# Left.net
KiCad netlist of a schematic drawn in Altium Designer
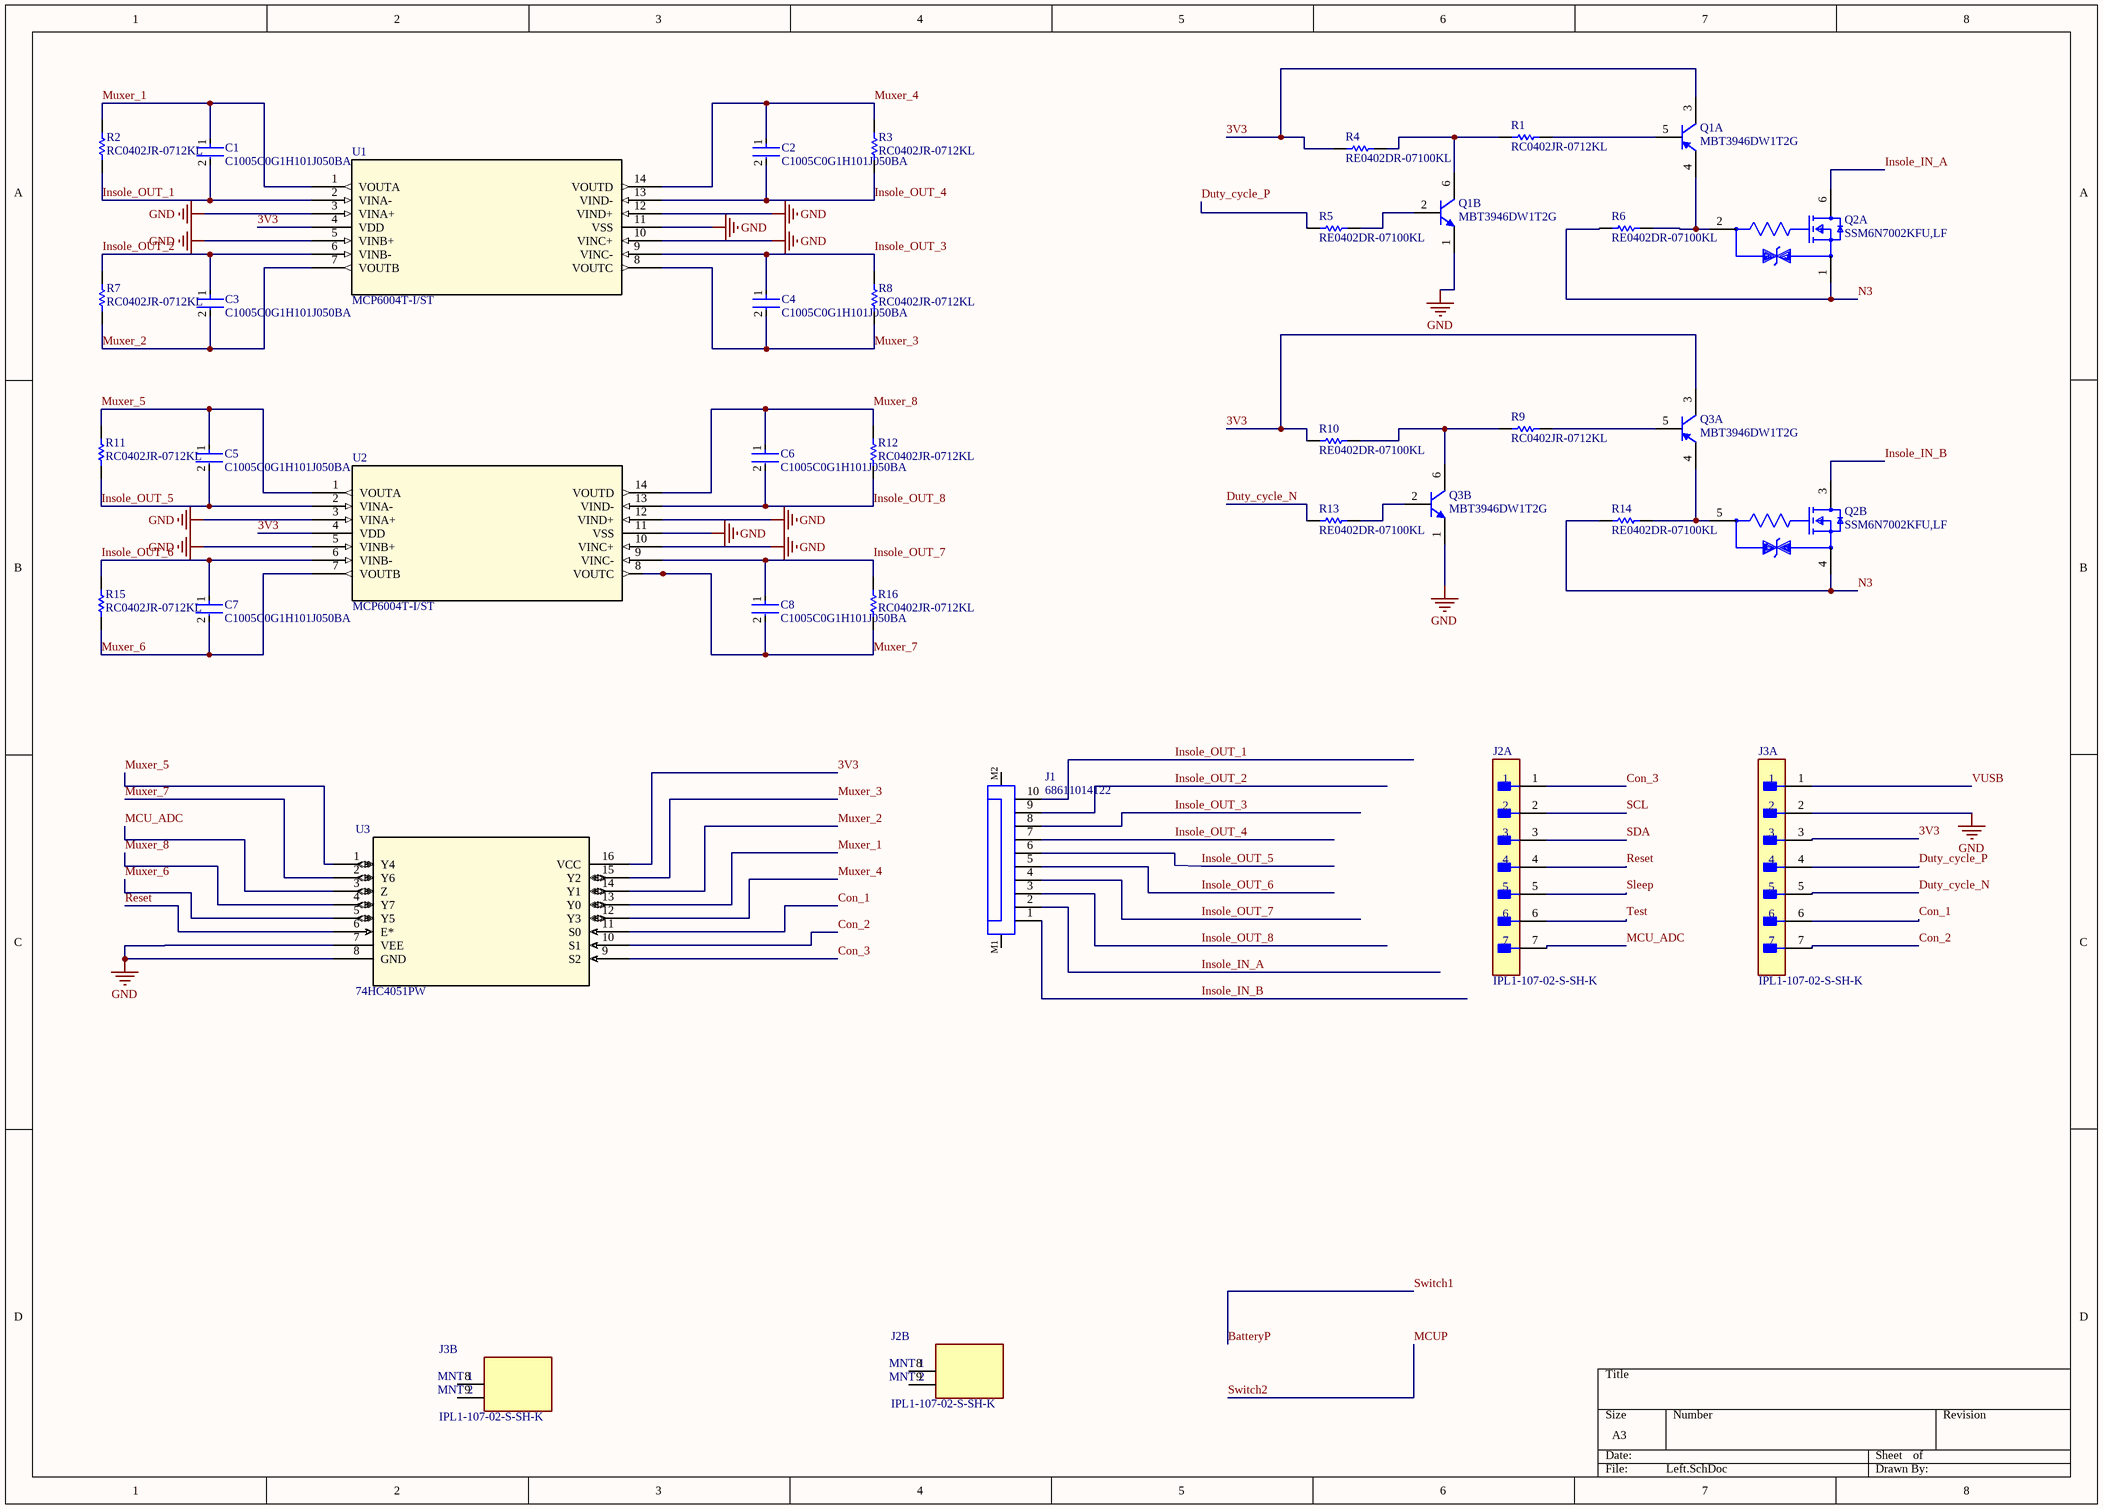
[diagram p0: Left.SchDoc]

(export (version "E")
  (design (tool "Eeschema 10.0.6"))
  (components
    (comp (ref "C1")
      (value "C1005C0G1H101J050BA")
      (footprint "FP-C1005-050-0_05-MFG")
      (description "Multilayer Ceramic Capacitors 100pF ±5% 50V C0G SMD 0402")
      (fields (field (name "TOLERANCE") "5%") (field (name "VOLTAGE") "50V"))
      (libsource (lib "Altium Content Vault") (part "b4654b650e69147ec39a6b967a45e02"))
    )
    (comp (ref "C2")
      (value "C1005C0G1H101J050BA")
      (footprint "FP-C1005-050-0_05-MFG")
      (description "Multilayer Ceramic Capacitors 100pF ±5% 50V C0G SMD 0402")
      (fields (field (name "TOLERANCE") "5%") (field (name "VOLTAGE") "50V"))
      (libsource (lib "Altium Content Vault") (part "b4654b650e69147ec39a6b967a45e02"))
    )
    (comp (ref "C3")
      (value "C1005C0G1H101J050BA")
      (footprint "FP-C1005-050-0_05-MFG")
      (description "Multilayer Ceramic Capacitors 100pF ±5% 50V C0G SMD 0402")
      (fields (field (name "TOLERANCE") "5%") (field (name "VOLTAGE") "50V"))
      (libsource (lib "Altium Content Vault") (part "b4654b650e69147ec39a6b967a45e02"))
    )
    (comp (ref "C4")
      (value "C1005C0G1H101J050BA")
      (footprint "FP-C1005-050-0_05-MFG")
      (description "Multilayer Ceramic Capacitors 100pF ±5% 50V C0G SMD 0402")
      (fields (field (name "TOLERANCE") "5%") (field (name "VOLTAGE") "50V"))
      (libsource (lib "Altium Content Vault") (part "b4654b650e69147ec39a6b967a45e02"))
    )
    (comp (ref "C5")
      (value "C1005C0G1H101J050BA")
      (footprint "FP-C1005-050-0_05-MFG")
      (description "Multilayer Ceramic Capacitors 100pF ±5% 50V C0G SMD 0402")
      (fields (field (name "TOLERANCE") "5%") (field (name "VOLTAGE") "50V"))
      (libsource (lib "Altium Content Vault") (part "b4654b650e69147ec39a6b967a45e02"))
    )
    (comp (ref "C6")
      (value "C1005C0G1H101J050BA")
      (footprint "FP-C1005-050-0_05-MFG")
      (description "Multilayer Ceramic Capacitors 100pF ±5% 50V C0G SMD 0402")
      (fields (field (name "TOLERANCE") "5%") (field (name "VOLTAGE") "50V"))
      (libsource (lib "Altium Content Vault") (part "b4654b650e69147ec39a6b967a45e02"))
    )
    (comp (ref "C7")
      (value "C1005C0G1H101J050BA")
      (footprint "FP-C1005-050-0_05-MFG")
      (description "Multilayer Ceramic Capacitors 100pF ±5% 50V C0G SMD 0402")
      (fields (field (name "TOLERANCE") "5%") (field (name "VOLTAGE") "50V"))
      (libsource (lib "Altium Content Vault") (part "b4654b650e69147ec39a6b967a45e02"))
    )
    (comp (ref "C8")
      (value "C1005C0G1H101J050BA")
      (footprint "FP-C1005-050-0_05-MFG")
      (description "Multilayer Ceramic Capacitors 100pF ±5% 50V C0G SMD 0402")
      (fields (field (name "TOLERANCE") "5%") (field (name "VOLTAGE") "50V"))
      (libsource (lib "Altium Content Vault") (part "b4654b650e69147ec39a6b967a45e02"))
    )
    (comp (ref "J1")
      (value "68611014122")
      (footprint "68611014122")
      (description "68611014122 FPC connect for left")
      (libsource (lib "Altium Content Vault") (part "FPC - 10P - 2MP"))
    )
    (comp (ref "J2")
      (value "IPL1-107-02-S-SH-K")
      (footprint "FP-IPL1-107-02-S-SH-K-0")
      (description "7 Position 1 Row .100\" (2.54 mm) pitch connector")
      (libsource (lib "Altium Content Vault") (part "780f130bdd63e82a3e741ceb73adf18"))
    )
    (comp (ref "J3")
      (value "IPL1-107-02-S-SH-K")
      (footprint "FP-IPL1-107-02-S-SH-K-0")
      (description "7 Position 1 Row .100\" (2.54 mm) pitch connector")
      (libsource (lib "Altium Content Vault") (part "780f130bdd63e82a3e741ceb73adf18"))
    )
    (comp (ref "Q1")
      (value "MBT3946DW1T2G")
      (footprint "ONSC-SC70-6-419B-02_W_V")
      (description "Complementary General Purpose Transistors, 6-Pin SC70, Pb-Free, Tape and Reel")
      (fields (field (name "MANUFACTURER") "On Semiconductor"))
      (libsource (lib "Altium Content Vault") (part "ONSC-NPN_PNP-6"))
    )
    (comp (ref "Q2")
      (value "SSM6N7002KFU,LF")
      (footprint "FP-SSOP6-P-0_65A-MFG")
      (description "MOSFET 2N-CH 60V 0.3A")
      (libsource (lib "Altium Content Vault") (part "088aa6ac103fdeebe0d1c52ece6b7b9"))
    )
    (comp (ref "Q3")
      (value "MBT3946DW1T2G")
      (footprint "ONSC-SC70-6-419B-02_W_V")
      (description "Complementary General Purpose Transistors, 6-Pin SC70, Pb-Free, Tape and Reel")
      (fields (field (name "MANUFACTURER") "On Semiconductor"))
      (libsource (lib "Altium Content Vault") (part "ONSC-NPN_PNP-6"))
    )
    (comp (ref "R1")
      (value "RC0402JR-0712KL")
      (footprint "RESC1005X40X25NL05T10")
      (description "12K resistor")
      (fields (field (name "MANUFACTURER") "Yageo / Phycomp"))
      (libsource (lib "Altium Content Vault") (part "RES"))
    )
    (comp (ref "R2")
      (value "RC0402JR-0712KL")
      (footprint "RESC1005X40X25NL05T10")
      (description "12K resistor")
      (fields (field (name "MANUFACTURER") "Yageo / Phycomp"))
      (libsource (lib "Altium Content Vault") (part "RES"))
    )
    (comp (ref "R3")
      (value "RC0402JR-0712KL")
      (footprint "RESC1005X40X25NL05T10")
      (description "12K resistor")
      (fields (field (name "MANUFACTURER") "Yageo / Phycomp"))
      (libsource (lib "Altium Content Vault") (part "RES"))
    )
    (comp (ref "R4")
      (value "RE0402DR-07100KL")
      (footprint "RESC1005X37X25ML05T10")
      (description "100K resistor")
      (fields (field (name "MANUFACTURER") "Yageo / Phycomp"))
      (libsource (lib "Altium Content Vault") (part "RES"))
    )
    (comp (ref "R5")
      (value "RE0402DR-07100KL")
      (footprint "RESC1005X37X25ML05T10")
      (description "100K resistor")
      (fields (field (name "MANUFACTURER") "Yageo / Phycomp"))
      (libsource (lib "Altium Content Vault") (part "RES"))
    )
    (comp (ref "R6")
      (value "RE0402DR-07100KL")
      (footprint "RESC1005X37X25ML05T10")
      (description "100K resistor")
      (fields (field (name "MANUFACTURER") "Yageo / Phycomp"))
      (libsource (lib "Altium Content Vault") (part "RES"))
    )
    (comp (ref "R7")
      (value "RC0402JR-0712KL")
      (footprint "RESC1005X40X25NL05T10")
      (description "12K resistor")
      (fields (field (name "MANUFACTURER") "Yageo / Phycomp"))
      (libsource (lib "Altium Content Vault") (part "RES"))
    )
    (comp (ref "R8")
      (value "RC0402JR-0712KL")
      (footprint "RESC1005X40X25NL05T10")
      (description "12K resistor")
      (fields (field (name "MANUFACTURER") "Yageo / Phycomp"))
      (libsource (lib "Altium Content Vault") (part "RES"))
    )
    (comp (ref "R9")
      (value "RC0402JR-0712KL")
      (footprint "RESC1005X40X25NL05T10")
      (description "12K resistor")
      (fields (field (name "MANUFACTURER") "Yageo / Phycomp"))
      (libsource (lib "Altium Content Vault") (part "RES"))
    )
    (comp (ref "R10")
      (value "RE0402DR-07100KL")
      (footprint "RESC1005X37X25ML05T10")
      (description "100K resistor")
      (fields (field (name "MANUFACTURER") "Yageo / Phycomp"))
      (libsource (lib "Altium Content Vault") (part "RES"))
    )
    (comp (ref "R11")
      (value "RC0402JR-0712KL")
      (footprint "RESC1005X40X25NL05T10")
      (description "12K resistor")
      (fields (field (name "MANUFACTURER") "Yageo / Phycomp"))
      (libsource (lib "Altium Content Vault") (part "RES"))
    )
    (comp (ref "R12")
      (value "RC0402JR-0712KL")
      (footprint "RESC1005X40X25NL05T10")
      (description "12K resistor")
      (fields (field (name "MANUFACTURER") "Yageo / Phycomp"))
      (libsource (lib "Altium Content Vault") (part "RES"))
    )
    (comp (ref "R13")
      (value "RE0402DR-07100KL")
      (footprint "RESC1005X37X25ML05T10")
      (description "100K resistor")
      (fields (field (name "MANUFACTURER") "Yageo / Phycomp"))
      (libsource (lib "Altium Content Vault") (part "RES"))
    )
    (comp (ref "R14")
      (value "RE0402DR-07100KL")
      (footprint "RESC1005X37X25ML05T10")
      (description "100K resistor")
      (fields (field (name "MANUFACTURER") "Yageo / Phycomp"))
      (libsource (lib "Altium Content Vault") (part "RES"))
    )
    (comp (ref "R15")
      (value "RC0402JR-0712KL")
      (footprint "RESC1005X40X25NL05T10")
      (description "12K resistor")
      (fields (field (name "MANUFACTURER") "Yageo / Phycomp"))
      (libsource (lib "Altium Content Vault") (part "RES"))
    )
    (comp (ref "R16")
      (value "RC0402JR-0712KL")
      (footprint "RESC1005X40X25NL05T10")
      (description "12K resistor")
      (fields (field (name "MANUFACTURER") "Yageo / Phycomp"))
      (libsource (lib "Altium Content Vault") (part "RES"))
    )
    (comp (ref "U1")
      (value "MCP6004T-I/ST")
      (footprint "TSSOP14_MC_MCH")
      (description "4-channel operational amplifer")
      (libsource (lib "MCP6004T-I&slash_ST") (part "MCP6004T-I/ST"))
    )
    (comp (ref "U2")
      (value "MCP6004T-I/ST")
      (footprint "TSSOP14_MC_MCH")
      (description "4-channel operational amplifer")
      (libsource (lib "MCP6004T-I&slash_ST") (part "MCP6004T-I/ST"))
    )
    (comp (ref "U3")
      (value "74HC4051PW")
      (footprint "SOT403-1_NXP")
      (description "8-channel analog multiplexer/demultiplexer")
      (fields (field (name "COPYRIGHT") "Copyright (C) 2023 Ultra Librarian. All rights reserved."))
      (libsource (lib "74HC4051PW") (part "74HC4051PW"))
    )
  )
  (nets
    (net (code "1") (name "/3V3") (class "Default")
      (node (ref "J3") (pin "3") (pinfunction "3_3") (pintype "passive"))
      (node (ref "Q1") (pin "3") (pinfunction "C_3") (pintype "passive"))
      (node (ref "Q3") (pin "3") (pinfunction "C_3") (pintype "passive"))
      (node (ref "R10") (pin "2") (pinfunction "2_2") (pintype "passive"))
      (node (ref "R4") (pin "2") (pinfunction "2_2") (pintype "passive"))
      (node (ref "U1") (pin "4") (pinfunction "VDD_4") (pintype "passive"))
      (node (ref "U2") (pin "4") (pinfunction "VDD_4") (pintype "passive"))
      (node (ref "U3") (pin "16") (pinfunction "VCC_16") (pintype "power_in"))
    )
    (net (code "3") (name "/Con_1") (class "Default")
      (node (ref "J3") (pin "6") (pinfunction "6_6") (pintype "passive"))
      (node (ref "U3") (pin "11") (pinfunction "S0_11") (pintype "input"))
    )
    (net (code "4") (name "/Con_2") (class "Default")
      (node (ref "J3") (pin "7") (pinfunction "7_7") (pintype "passive"))
      (node (ref "U3") (pin "10") (pinfunction "S1_10") (pintype "input"))
    )
    (net (code "5") (name "/Con_3") (class "Default")
      (node (ref "J2") (pin "1") (pinfunction "1_1") (pintype "passive"))
      (node (ref "U3") (pin "9") (pinfunction "S2_9") (pintype "input"))
    )
    (net (code "6") (name "/Duty_cycle_N") (class "Default")
      (node (ref "J3") (pin "5") (pinfunction "5_5") (pintype "passive"))
      (node (ref "R13") (pin "2") (pinfunction "2_2") (pintype "passive"))
    )
    (net (code "7") (name "/Duty_cycle_P") (class "Default")
      (node (ref "J3") (pin "4") (pinfunction "4_4") (pintype "passive"))
      (node (ref "R5") (pin "2") (pinfunction "2_2") (pintype "passive"))
    )
    (net (code "8") (name "/Insole_IN_A") (class "Default")
      (node (ref "J1") (pin "2") (pinfunction "2_2") (pintype "passive"))
      (node (ref "Q2") (pin "6") (pinfunction "Drain1_6") (pintype "passive"))
    )
    (net (code "9") (name "/Insole_IN_B") (class "Default")
      (node (ref "J1") (pin "1") (pinfunction "1_1") (pintype "passive"))
      (node (ref "Q2") (pin "3") (pinfunction "Drain2_3") (pintype "passive"))
    )
    (net (code "10") (name "/Insole_OUT_1") (class "Default")
      (node (ref "C1") (pin "2") (pinfunction "2_2") (pintype "passive"))
      (node (ref "J1") (pin "10") (pinfunction "10_10") (pintype "passive"))
      (node (ref "R2") (pin "1") (pinfunction "1_1") (pintype "passive"))
      (node (ref "U1") (pin "2") (pinfunction "VINA-_2") (pintype "input"))
    )
    (net (code "11") (name "/Insole_OUT_2") (class "Default")
      (node (ref "C3") (pin "1") (pinfunction "1_1") (pintype "passive"))
      (node (ref "J1") (pin "9") (pinfunction "9_9") (pintype "passive"))
      (node (ref "R7") (pin "2") (pinfunction "2_2") (pintype "passive"))
      (node (ref "U1") (pin "6") (pinfunction "VINB-_6") (pintype "input"))
    )
    (net (code "12") (name "/Insole_OUT_3") (class "Default")
      (node (ref "C4") (pin "1") (pinfunction "1_1") (pintype "passive"))
      (node (ref "J1") (pin "8") (pinfunction "8_8") (pintype "passive"))
      (node (ref "R8") (pin "2") (pinfunction "2_2") (pintype "passive"))
      (node (ref "U1") (pin "9") (pinfunction "VINC-_9") (pintype "input"))
    )
    (net (code "13") (name "/Insole_OUT_4") (class "Default")
      (node (ref "C2") (pin "2") (pinfunction "2_2") (pintype "passive"))
      (node (ref "J1") (pin "7") (pinfunction "7_7") (pintype "passive"))
      (node (ref "R3") (pin "1") (pinfunction "1_1") (pintype "passive"))
      (node (ref "U1") (pin "13") (pinfunction "VIND-_13") (pintype "input"))
    )
    (net (code "14") (name "/Insole_OUT_5") (class "Default")
      (node (ref "C5") (pin "2") (pinfunction "2_2") (pintype "passive"))
      (node (ref "J1") (pin "6") (pinfunction "6_6") (pintype "passive"))
      (node (ref "R11") (pin "1") (pinfunction "1_1") (pintype "passive"))
      (node (ref "U2") (pin "2") (pinfunction "VINA-_2") (pintype "input"))
    )
    (net (code "15") (name "/Insole_OUT_6") (class "Default")
      (node (ref "C7") (pin "1") (pinfunction "1_1") (pintype "passive"))
      (node (ref "J1") (pin "5") (pinfunction "5_5") (pintype "passive"))
      (node (ref "R15") (pin "2") (pinfunction "2_2") (pintype "passive"))
      (node (ref "U2") (pin "6") (pinfunction "VINB-_6") (pintype "input"))
    )
    (net (code "16") (name "/Insole_OUT_7") (class "Default")
      (node (ref "C8") (pin "1") (pinfunction "1_1") (pintype "passive"))
      (node (ref "J1") (pin "4") (pinfunction "4_4") (pintype "passive"))
      (node (ref "R16") (pin "2") (pinfunction "2_2") (pintype "passive"))
      (node (ref "U2") (pin "9") (pinfunction "VINC-_9") (pintype "input"))
    )
    (net (code "17") (name "/Insole_OUT_8") (class "Default")
      (node (ref "C6") (pin "2") (pinfunction "2_2") (pintype "passive"))
      (node (ref "J1") (pin "3") (pinfunction "3_3") (pintype "passive"))
      (node (ref "R12") (pin "1") (pinfunction "1_1") (pintype "passive"))
      (node (ref "U2") (pin "13") (pinfunction "VIND-_13") (pintype "input"))
    )
    (net (code "19") (name "/MCU_ADC") (class "Default")
      (node (ref "J2") (pin "7") (pinfunction "7_7") (pintype "passive"))
      (node (ref "U3") (pin "3") (pinfunction "Z_3") (pintype "bidirectional"))
    )
    (net (code "20") (name "/Muxer_1") (class "Default")
      (node (ref "C1") (pin "1") (pinfunction "1_1") (pintype "passive"))
      (node (ref "R2") (pin "2") (pinfunction "2_2") (pintype "passive"))
      (node (ref "U1") (pin "1") (pinfunction "VOUTA_1") (pintype "output"))
      (node (ref "U3") (pin "13") (pinfunction "Y0_13") (pintype "bidirectional"))
    )
    (net (code "21") (name "/Muxer_2") (class "Default")
      (node (ref "C3") (pin "2") (pinfunction "2_2") (pintype "passive"))
      (node (ref "R7") (pin "1") (pinfunction "1_1") (pintype "passive"))
      (node (ref "U1") (pin "7") (pinfunction "VOUTB_7") (pintype "output"))
      (node (ref "U3") (pin "14") (pinfunction "Y1_14") (pintype "bidirectional"))
    )
    (net (code "22") (name "/Muxer_3") (class "Default")
      (node (ref "C4") (pin "2") (pinfunction "2_2") (pintype "passive"))
      (node (ref "R8") (pin "1") (pinfunction "1_1") (pintype "passive"))
      (node (ref "U1") (pin "8") (pinfunction "VOUTC_8") (pintype "output"))
      (node (ref "U3") (pin "15") (pinfunction "Y2_15") (pintype "bidirectional"))
    )
    (net (code "23") (name "/Muxer_4") (class "Default")
      (node (ref "C2") (pin "1") (pinfunction "1_1") (pintype "passive"))
      (node (ref "R3") (pin "2") (pinfunction "2_2") (pintype "passive"))
      (node (ref "U1") (pin "14") (pinfunction "VOUTD_14") (pintype "output"))
      (node (ref "U3") (pin "12") (pinfunction "Y3_12") (pintype "bidirectional"))
    )
    (net (code "24") (name "/Muxer_5") (class "Default")
      (node (ref "C5") (pin "1") (pinfunction "1_1") (pintype "passive"))
      (node (ref "R11") (pin "2") (pinfunction "2_2") (pintype "passive"))
      (node (ref "U2") (pin "1") (pinfunction "VOUTA_1") (pintype "output"))
      (node (ref "U3") (pin "1") (pinfunction "Y4_1") (pintype "bidirectional"))
    )
    (net (code "25") (name "/Muxer_6") (class "Default")
      (node (ref "C7") (pin "2") (pinfunction "2_2") (pintype "passive"))
      (node (ref "R15") (pin "1") (pinfunction "1_1") (pintype "passive"))
      (node (ref "U2") (pin "7") (pinfunction "VOUTB_7") (pintype "output"))
      (node (ref "U3") (pin "5") (pinfunction "Y5_5") (pintype "bidirectional"))
    )
    (net (code "26") (name "/Muxer_7") (class "Default")
      (node (ref "C8") (pin "2") (pinfunction "2_2") (pintype "passive"))
      (node (ref "R16") (pin "1") (pinfunction "1_1") (pintype "passive"))
      (node (ref "U2") (pin "8") (pinfunction "VOUTC_8") (pintype "output"))
      (node (ref "U3") (pin "2") (pinfunction "Y6_2") (pintype "bidirectional"))
    )
    (net (code "27") (name "/Muxer_8") (class "Default")
      (node (ref "C6") (pin "1") (pinfunction "1_1") (pintype "passive"))
      (node (ref "R12") (pin "2") (pinfunction "2_2") (pintype "passive"))
      (node (ref "U2") (pin "14") (pinfunction "VOUTD_14") (pintype "output"))
      (node (ref "U3") (pin "4") (pinfunction "Y7_4") (pintype "bidirectional"))
    )
    (net (code "28") (name "/N3") (class "Default")
      (node (ref "Q2") (pin "1") (pinfunction "Source1_1") (pintype "passive"))
      (node (ref "Q2") (pin "4") (pinfunction "Source2_4") (pintype "passive"))
      (node (ref "R14") (pin "2") (pinfunction "2_2") (pintype "passive"))
      (node (ref "R6") (pin "2") (pinfunction "2_2") (pintype "passive"))
    )
    (net (code "29") (name "/Reset") (class "Default")
      (node (ref "J2") (pin "4") (pinfunction "4_4") (pintype "passive"))
      (node (ref "U3") (pin "6") (pinfunction "E*_6") (pintype "input"))
    )
    (net (code "30") (name "/SCL") (class "Default")
      (node (ref "J2") (pin "2") (pinfunction "2_2") (pintype "passive"))
    )
    (net (code "31") (name "/SDA") (class "Default")
      (node (ref "J2") (pin "3") (pinfunction "3_3") (pintype "passive"))
    )
    (net (code "32") (name "/Sleep") (class "Default")
      (node (ref "J2") (pin "5") (pinfunction "5_5") (pintype "passive"))
    )
    (net (code "33") (name "/Test") (class "Default")
      (node (ref "J2") (pin "6") (pinfunction "6_6") (pintype "passive"))
    )
    (net (code "34") (name "/VUSB") (class "Default")
      (node (ref "J3") (pin "1") (pinfunction "1_1") (pintype "passive"))
    )
    (net (code "35") (name "GND") (class "Default")
      (node (ref "J3") (pin "2") (pinfunction "2_2") (pintype "passive"))
      (node (ref "Q1") (pin "1") (pinfunction "E_1") (pintype "passive"))
      (node (ref "Q3") (pin "1") (pinfunction "E_1") (pintype "passive"))
      (node (ref "U1") (pin "10") (pinfunction "VINC+_10") (pintype "input"))
      (node (ref "U1") (pin "11") (pinfunction "VSS_11") (pintype "passive"))
      (node (ref "U1") (pin "12") (pinfunction "VIND+_12") (pintype "input"))
      (node (ref "U1") (pin "3") (pinfunction "VINA+_3") (pintype "input"))
      (node (ref "U1") (pin "5") (pinfunction "VINB+_5") (pintype "input"))
      (node (ref "U2") (pin "10") (pinfunction "VINC+_10") (pintype "input"))
      (node (ref "U2") (pin "11") (pinfunction "VSS_11") (pintype "passive"))
      (node (ref "U2") (pin "12") (pinfunction "VIND+_12") (pintype "input"))
      (node (ref "U2") (pin "3") (pinfunction "VINA+_3") (pintype "input"))
      (node (ref "U2") (pin "5") (pinfunction "VINB+_5") (pintype "input"))
      (node (ref "U3") (pin "7") (pinfunction "VEE_7") (pintype "power_in"))
      (node (ref "U3") (pin "8") (pinfunction "GND_8") (pintype "power_in"))
    )
    (net (code "36") (name "Net-(Q1A-B)") (class "Default")
      (node (ref "Q1") (pin "5") (pinfunction "B_5") (pintype "passive"))
      (node (ref "R1") (pin "1") (pinfunction "1_1") (pintype "passive"))
    )
    (net (code "37") (name "Net-(Q1A-E)") (class "Default")
      (node (ref "Q1") (pin "4") (pinfunction "E_4") (pintype "passive"))
      (node (ref "Q2") (pin "2") (pinfunction "Gate1_2") (pintype "passive"))
      (node (ref "R6") (pin "1") (pinfunction "1_1") (pintype "passive"))
    )
    (net (code "38") (name "Net-(Q1B-B)") (class "Default")
      (node (ref "Q1") (pin "2") (pinfunction "B_2") (pintype "passive"))
      (node (ref "R5") (pin "1") (pinfunction "1_1") (pintype "passive"))
    )
    (net (code "39") (name "Net-(Q1B-C)") (class "Default")
      (node (ref "Q1") (pin "6") (pinfunction "C_6") (pintype "passive"))
      (node (ref "R1") (pin "2") (pinfunction "2_2") (pintype "passive"))
      (node (ref "R4") (pin "1") (pinfunction "1_1") (pintype "passive"))
    )
    (net (code "40") (name "Net-(Q2B-Gate2)") (class "Default")
      (node (ref "Q2") (pin "5") (pinfunction "Gate2_5") (pintype "passive"))
      (node (ref "Q3") (pin "4") (pinfunction "E_4") (pintype "passive"))
      (node (ref "R14") (pin "1") (pinfunction "1_1") (pintype "passive"))
    )
    (net (code "41") (name "Net-(Q3A-B)") (class "Default")
      (node (ref "Q3") (pin "5") (pinfunction "B_5") (pintype "passive"))
      (node (ref "R9") (pin "1") (pinfunction "1_1") (pintype "passive"))
    )
    (net (code "42") (name "Net-(Q3B-B)") (class "Default")
      (node (ref "Q3") (pin "2") (pinfunction "B_2") (pintype "passive"))
      (node (ref "R13") (pin "1") (pinfunction "1_1") (pintype "passive"))
    )
    (net (code "43") (name "Net-(Q3B-C)") (class "Default")
      (node (ref "Q3") (pin "6") (pinfunction "C_6") (pintype "passive"))
      (node (ref "R10") (pin "1") (pinfunction "1_1") (pintype "passive"))
      (node (ref "R9") (pin "2") (pinfunction "2_2") (pintype "passive"))
    )
    (net (code "44") (name "unconnected-(J1-PadM1)") (class "Default")
      (node (ref "J1") (pin "M1") (pinfunction "M1_M1") (pintype "passive"))
    )
    (net (code "45") (name "unconnected-(J1-PadM2)") (class "Default")
      (node (ref "J1") (pin "M2") (pinfunction "M2_M2") (pintype "passive"))
    )
    (net (code "46") (name "unconnected-(J2B-MNT_1-Pad8)") (class "Default")
      (node (ref "J2") (pin "8") (pinfunction "MNT_1_8") (pintype "passive"))
    )
    (net (code "47") (name "unconnected-(J2B-MNT_2-Pad9)") (class "Default")
      (node (ref "J2") (pin "9") (pinfunction "MNT_2_9") (pintype "passive"))
    )
    (net (code "48") (name "unconnected-(J3B-MNT_1-Pad8)") (class "Default")
      (node (ref "J3") (pin "8") (pinfunction "MNT_1_8") (pintype "passive"))
    )
    (net (code "49") (name "unconnected-(J3B-MNT_2-Pad9)") (class "Default")
      (node (ref "J3") (pin "9") (pinfunction "MNT_2_9") (pintype "passive"))
    )
  )
)
